# Level_Shifter.net
KiCad netlist of a schematic drawn in Altium Designer
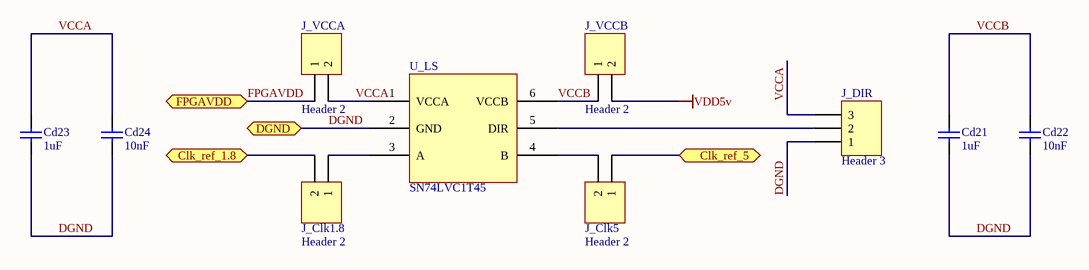
[diagram p0: Level_Shifter.SchDoc]

(export (version "E")
  (design (tool "Eeschema 10.0.6"))
  (components
    (comp (ref "Cd21")
      (value "1uF")
      (footprint "1608[0603]")
      (description "Capacitor")
      (fields (field (name "Comment") "Cap") (field (name "PUBLISHER") "Altium Limited"))
      (libsource (lib "Miscellaneous Devices") (part "Cap"))
    )
    (comp (ref "Cd22")
      (value "10nF")
      (footprint "1608[0603]")
      (description "Capacitor")
      (fields (field (name "Comment") "Cap") (field (name "PUBLISHER") "Altium Limited"))
      (libsource (lib "Miscellaneous Devices") (part "Cap"))
    )
    (comp (ref "Cd23")
      (value "1uF")
      (footprint "1608[0603]")
      (description "Capacitor")
      (fields (field (name "Comment") "Cap") (field (name "PUBLISHER") "Altium Limited"))
      (libsource (lib "Miscellaneous Devices") (part "Cap"))
    )
    (comp (ref "Cd24")
      (value "10nF")
      (footprint "1608[0603]")
      (description "Capacitor")
      (fields (field (name "Comment") "Cap") (field (name "PUBLISHER") "Altium Limited"))
      (libsource (lib "Miscellaneous Devices") (part "Cap"))
    )
    (comp (ref "J_Clk1.8")
      (value "Header 2")
      (footprint "HDR1X2")
      (description "Header, 2-Pin")
      (fields (field (name "PUBLISHER") "Altium Limited"))
      (libsource (lib "Miscellaneous Connectors") (part "Header 2"))
    )
    (comp (ref "J_Clk5")
      (value "Header 2")
      (footprint "HDR1X2")
      (description "Header, 2-Pin")
      (fields (field (name "PUBLISHER") "Altium Limited"))
      (libsource (lib "Miscellaneous Connectors") (part "Header 2"))
    )
    (comp (ref "J_DIR")
      (value "Header 3")
      (footprint "HDR1X3")
      (description "Header, 3-Pin")
      (fields (field (name "PUBLISHER") "Altium Limited"))
      (libsource (lib "Miscellaneous Connectors") (part "Header 3"))
    )
    (comp (ref "J_VCCA")
      (value "Header 2")
      (footprint "HDR1X2")
      (description "Header, 2-Pin")
      (fields (field (name "PUBLISHER") "Altium Limited"))
      (libsource (lib "") (part "Header 2_1"))
    )
    (comp (ref "J_VCCB")
      (value "Header 2")
      (footprint "HDR1X2")
      (description "Header, 2-Pin")
      (fields (field (name "PUBLISHER") "Altium Limited"))
      (libsource (lib "") (part "Header 2_1"))
    )
    (comp (ref "U_LS")
      (value "SN74LVC1T45")
      (footprint "SO-G6/P.95")
      (libsource (lib "custom") (part "SN74LVC1T45"))
    )
  )
  (nets
    (net (code "1") (name "/Clk_ref_1.8") (class "Default")
      (node (ref "J_Clk1.8") (pin "2") (pinfunction "2_2") (pintype "passive"))
    )
    (net (code "2") (name "/Clk_ref_5") (class "Default")
      (node (ref "J_Clk5") (pin "1") (pinfunction "1_1") (pintype "passive"))
    )
    (net (code "3") (name "/DGND") (class "Default")
      (node (ref "Cd21") (pin "2") (pinfunction "2_2") (pintype "passive"))
      (node (ref "Cd22") (pin "2") (pinfunction "2_2") (pintype "passive"))
      (node (ref "Cd23") (pin "2") (pinfunction "2_2") (pintype "passive"))
      (node (ref "Cd24") (pin "2") (pinfunction "2_2") (pintype "passive"))
      (node (ref "J_DIR") (pin "1") (pinfunction "1_1") (pintype "passive"))
      (node (ref "U_LS") (pin "2") (pinfunction "GND_2") (pintype "passive"))
    )
    (net (code "4") (name "/FPGAVDD") (class "Default")
      (node (ref "J_VCCA") (pin "1") (pinfunction "1_1") (pintype "passive"))
    )
    (net (code "5") (name "/VCCA") (class "Default")
      (node (ref "Cd23") (pin "1") (pinfunction "1_1") (pintype "passive"))
      (node (ref "Cd24") (pin "1") (pinfunction "1_1") (pintype "passive"))
      (node (ref "J_DIR") (pin "3") (pinfunction "3_3") (pintype "passive"))
      (node (ref "J_VCCA") (pin "2") (pinfunction "2_2") (pintype "passive"))
      (node (ref "U_LS") (pin "1") (pinfunction "VCCA_1") (pintype "passive"))
    )
    (net (code "6") (name "/VCCB") (class "Default")
      (node (ref "Cd21") (pin "1") (pinfunction "1_1") (pintype "passive"))
      (node (ref "Cd22") (pin "1") (pinfunction "1_1") (pintype "passive"))
      (node (ref "J_VCCB") (pin "1") (pinfunction "1_1") (pintype "passive"))
      (node (ref "U_LS") (pin "6") (pinfunction "VCCB_6") (pintype "passive"))
    )
    (net (code "7") (name "Net-(U_LS-A)") (class "Default")
      (node (ref "J_Clk1.8") (pin "1") (pinfunction "1_1") (pintype "passive"))
      (node (ref "U_LS") (pin "3") (pinfunction "A_3") (pintype "passive"))
    )
    (net (code "8") (name "Net-(U_LS-B)") (class "Default")
      (node (ref "J_Clk5") (pin "2") (pinfunction "2_2") (pintype "passive"))
      (node (ref "U_LS") (pin "4") (pinfunction "B_4") (pintype "passive"))
    )
    (net (code "9") (name "Net-(U_LS-DIR)") (class "Default")
      (node (ref "J_DIR") (pin "2") (pinfunction "2_2") (pintype "passive"))
      (node (ref "U_LS") (pin "5") (pinfunction "DIR_5") (pintype "passive"))
    )
    (net (code "10") (name "VDD5v") (class "Default")
      (node (ref "J_VCCB") (pin "2") (pinfunction "2_2") (pintype "passive"))
    )
  )
)
